# traning_shield_ver2.net
KiCad netlist of a schematic drawn in EAGLE
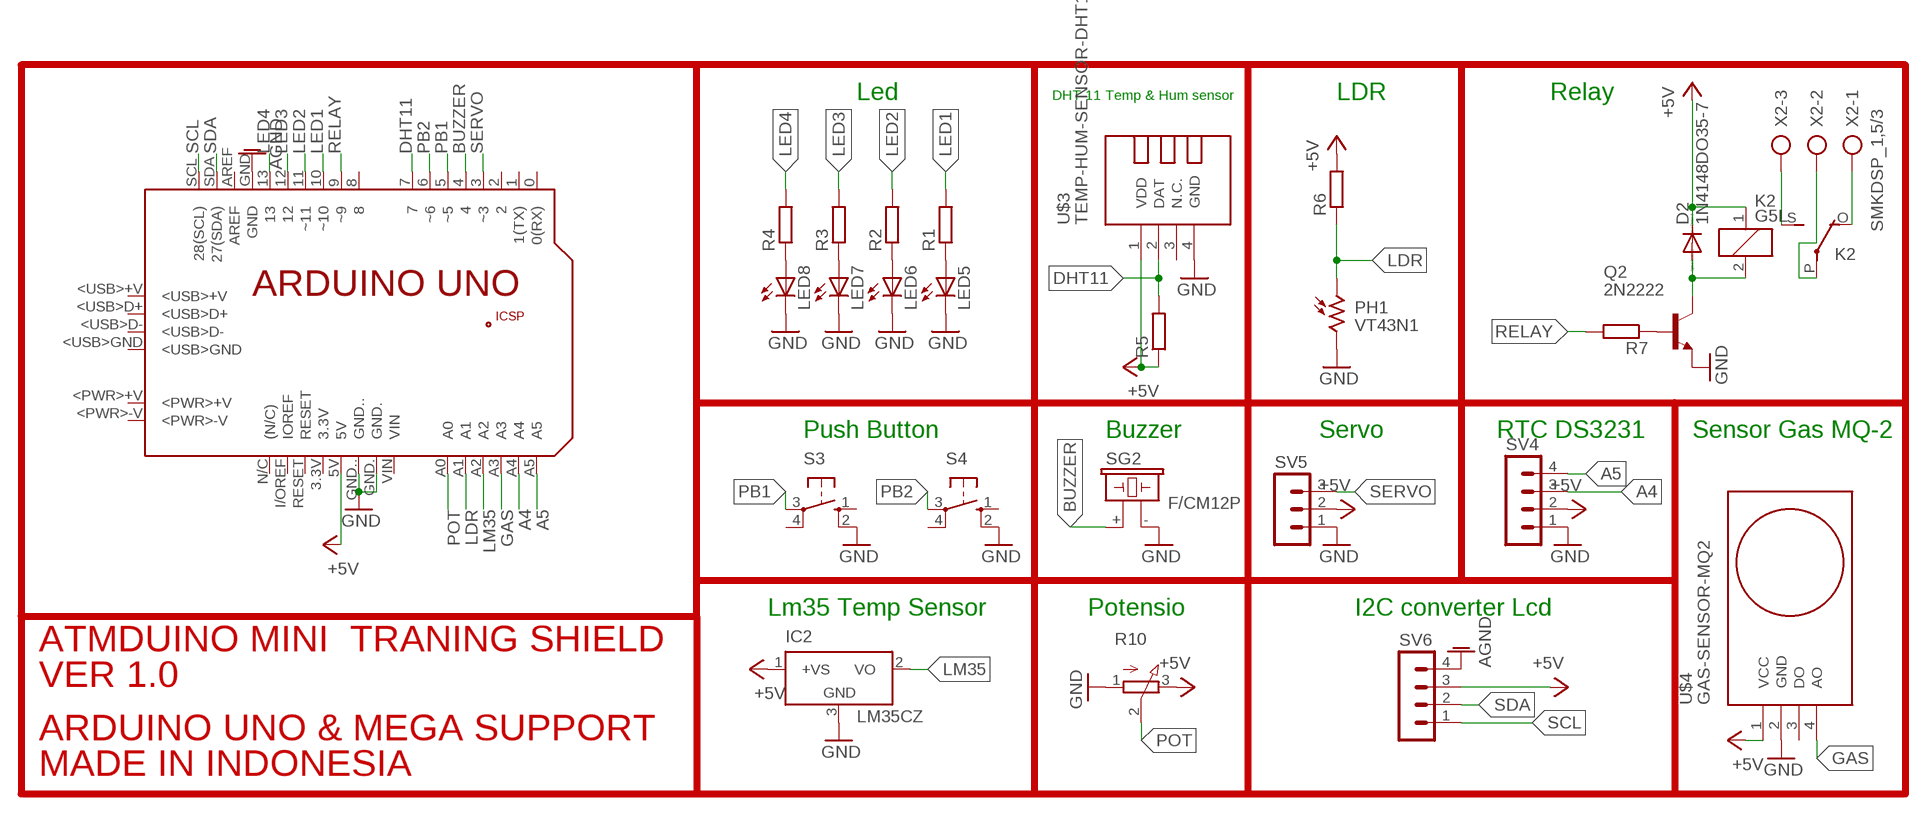
[diagram p0: schematic, sheet 1]

(export (version "E")
  (design (tool "Eeschema 10.0.6"))
  (components
    (comp (ref "D2")
      (value "1N4148DO35-7")
      (footprint "eagle-import:DO35-7")
      (libsource (lib "eagle-import") (part "1N4148DO35-7"))
    )
    (comp (ref "IC2")
      (value "LM35CZ")
      (footprint "eagle-import:TO92")
      (libsource (lib "eagle-import") (part "LM35CZ"))
    )
    (comp (ref "K2")
      (value "G5L")
      (footprint "eagle-import:G5LE")
      (libsource (lib "eagle-import") (part "G5L"))
    )
    (comp (ref "LED5")
      (value "LED5MM")
      (footprint "eagle-import:LED5MM")
      (libsource (lib "eagle-import") (part "LED5MM"))
    )
    (comp (ref "LED6")
      (value "LED5MM")
      (footprint "eagle-import:LED5MM")
      (libsource (lib "eagle-import") (part "LED5MM"))
    )
    (comp (ref "LED7")
      (value "LED5MM")
      (footprint "eagle-import:LED5MM")
      (libsource (lib "eagle-import") (part "LED5MM"))
    )
    (comp (ref "LED8")
      (value "LED5MM")
      (footprint "eagle-import:LED5MM")
      (libsource (lib "eagle-import") (part "LED5MM"))
    )
    (comp (ref "PCB2")
      (value "ARDUINO_UNO")
      (footprint "eagle-import:ARDUINO_UNO")
      (libsource (lib "eagle-import") (part "ARDUINO_UNO"))
    )
    (comp (ref "PH1")
      (value "VT43N1")
      (footprint "eagle-import:VT400")
      (libsource (lib "eagle-import") (part "VT43N1"))
    )
    (comp (ref "Q2")
      (value "2N2222")
      (footprint "eagle-import:TO18")
      (libsource (lib "eagle-import") (part "2N2222"))
    )
    (comp (ref "R1")
      (value "R-EU_0204/7")
      (footprint "eagle-import:0204_7")
      (libsource (lib "eagle-import") (part "R-EU_0204/7"))
    )
    (comp (ref "R2")
      (value "R-EU_0204/7")
      (footprint "eagle-import:0204_7")
      (libsource (lib "eagle-import") (part "R-EU_0204/7"))
    )
    (comp (ref "R3")
      (value "R-EU_0204/7")
      (footprint "eagle-import:0204_7")
      (libsource (lib "eagle-import") (part "R-EU_0204/7"))
    )
    (comp (ref "R4")
      (value "R-EU_0204/7")
      (footprint "eagle-import:0204_7")
      (libsource (lib "eagle-import") (part "R-EU_0204/7"))
    )
    (comp (ref "R5")
      (value "R-EU_0204/7")
      (footprint "eagle-import:0204_7")
      (libsource (lib "eagle-import") (part "R-EU_0204/7"))
    )
    (comp (ref "R6")
      (value "R-EU_0204/7")
      (footprint "eagle-import:0204_7")
      (libsource (lib "eagle-import") (part "R-EU_0204/7"))
    )
    (comp (ref "R7")
      (value "R-EU_0204/7")
      (footprint "eagle-import:0204_7")
      (libsource (lib "eagle-import") (part "R-EU_0204/7"))
    )
    (comp (ref "R10")
      (value "3RP/1610N")
      (footprint "eagle-import:3RP_1610N")
      (libsource (lib "eagle-import") (part "3RP/1610N"))
    )
    (comp (ref "S3")
      (value "10-XX")
      (footprint "eagle-import:B3F-10XX")
      (fields (field (name "MPN") "B3F-1000"))
      (libsource (lib "eagle-import") (part "10-XX"))
    )
    (comp (ref "S4")
      (value "10-XX")
      (footprint "eagle-import:B3F-10XX")
      (fields (field (name "MPN") "B3F-1000"))
      (libsource (lib "eagle-import") (part "10-XX"))
    )
    (comp (ref "SG2")
      (value "F/CM12P")
      (footprint "eagle-import:F_CM12P")
      (libsource (lib "eagle-import") (part "F/CM12P"))
    )
    (comp (ref "SV4")
      (value "MA04-1")
      (footprint "eagle-import:MA04-1")
      (libsource (lib "eagle-import") (part "MA04-1"))
    )
    (comp (ref "SV5")
      (value "MA03-1")
      (footprint "eagle-import:MA03-1")
      (libsource (lib "eagle-import") (part "MA03-1"))
    )
    (comp (ref "SV6")
      (value "MA04-1")
      (footprint "eagle-import:MA04-1")
      (libsource (lib "eagle-import") (part "MA04-1"))
    )
    (comp (ref "U$3")
      (value "TEMP-HUM-SENSOR-DHT11")
      (footprint "eagle-import:TEMP-HUM-SENSOR-DHT11")
      (libsource (lib "eagle-import") (part "TEMP-HUM-SENSOR-DHT11"))
    )
    (comp (ref "U$4")
      (value "GAS-SENSOR-MQ2")
      (footprint "eagle-import:GAS-SENSOR-MQ2")
      (libsource (lib "eagle-import") (part "GAS-SENSOR-MQ2"))
    )
    (comp (ref "X2")
      (value "SMKDSP_1,5/3")
      (footprint "eagle-import:SMKDSP_1,5_3")
      (fields (field (name "MF") "FARNELL") (field (name "MPN") "1733583"))
      (libsource (lib "eagle-import") (part "SMKDSP_1,5/3"))
    )
  )
  (nets
    (net (code "1") (name "+5V") (class "Default")
      (node (ref "D2") (pin "C") (pinfunction "C_C") (pintype "passive"))
      (node (ref "IC2") (pin "1") (pinfunction "+VS_1") (pintype "input"))
      (node (ref "K2") (pin "1") (pinfunction "1_1") (pintype "passive"))
      (node (ref "PCB2") (pin "5V") (pinfunction "5V_5V") (pintype "bidirectional"))
      (node (ref "R10") (pin "3") (pinfunction "E_3") (pintype "passive"))
      (node (ref "R5") (pin "1") (pinfunction "1_1") (pintype "passive"))
      (node (ref "R6") (pin "2") (pinfunction "2_2") (pintype "passive"))
      (node (ref "SV4") (pin "2") (pinfunction "2_2") (pintype "passive"))
      (node (ref "SV5") (pin "2") (pinfunction "2_2") (pintype "passive"))
      (node (ref "SV6") (pin "3") (pinfunction "3_3") (pintype "passive"))
      (node (ref "U$3") (pin "1") (pinfunction "VDD_1") (pintype "power_in"))
      (node (ref "U$4") (pin "1") (pinfunction "VCC_1") (pintype "power_in"))
    )
    (net (code "2") (name "A4") (class "Default")
      (node (ref "PCB2") (pin "A4") (pinfunction "A4_A4") (pintype "bidirectional"))
      (node (ref "SV4") (pin "3") (pinfunction "3_3") (pintype "passive"))
    )
    (net (code "3") (name "A5") (class "Default")
      (node (ref "PCB2") (pin "A5") (pinfunction "A5_A5") (pintype "bidirectional"))
      (node (ref "SV4") (pin "4") (pinfunction "4_4") (pintype "passive"))
    )
    (net (code "4") (name "AGND") (class "Default")
      (node (ref "PCB2") (pin "GND") (pinfunction "GND_GND") (pintype "bidirectional"))
      (node (ref "SV6") (pin "4") (pinfunction "4_4") (pintype "passive"))
    )
    (net (code "5") (name "BUZZER") (class "Default")
      (node (ref "PCB2") (pin "4") (pinfunction "4_4") (pintype "bidirectional"))
      (node (ref "SG2") (pin "+") (pinfunction "1_+") (pintype "passive"))
    )
    (net (code "6") (name "DHT11") (class "Default")
      (node (ref "PCB2") (pin "7") (pinfunction "7_7") (pintype "bidirectional"))
      (node (ref "R5") (pin "2") (pinfunction "2_2") (pintype "passive"))
      (node (ref "U$3") (pin "2") (pinfunction "DAT_2") (pintype "bidirectional"))
    )
    (net (code "7") (name "GAS") (class "Default")
      (node (ref "PCB2") (pin "A3") (pinfunction "A3_A3") (pintype "bidirectional"))
      (node (ref "U$4") (pin "4") (pinfunction "AO_4") (pintype "output"))
    )
    (net (code "8") (name "GND") (class "Default")
      (node (ref "IC2") (pin "3") (pinfunction "GND_3") (pintype "power_in"))
      (node (ref "LED5") (pin "K") (pinfunction "C_K") (pintype "passive"))
      (node (ref "LED6") (pin "K") (pinfunction "C_K") (pintype "passive"))
      (node (ref "LED7") (pin "K") (pinfunction "C_K") (pintype "passive"))
      (node (ref "LED8") (pin "K") (pinfunction "C_K") (pintype "passive"))
      (node (ref "PCB2") (pin "GND.") (pinfunction "GND._GND.") (pintype "bidirectional"))
      (node (ref "PCB2") (pin "GND..") (pinfunction "GND.._GND..") (pintype "bidirectional"))
      (node (ref "PH1") (pin "2") (pinfunction "2_2") (pintype "passive"))
      (node (ref "Q2") (pin "1") (pinfunction "E_1") (pintype "passive"))
      (node (ref "R10") (pin "1") (pinfunction "A_1") (pintype "passive"))
      (node (ref "S3") (pin "2") (pinfunction "S1_2") (pintype "passive"))
      (node (ref "S4") (pin "2") (pinfunction "S1_2") (pintype "passive"))
      (node (ref "SG2") (pin "-") (pinfunction "2_-") (pintype "passive"))
      (node (ref "SV4") (pin "1") (pinfunction "1_1") (pintype "passive"))
      (node (ref "SV5") (pin "1") (pinfunction "1_1") (pintype "passive"))
      (node (ref "U$3") (pin "4") (pinfunction "GND_4") (pintype "power_in"))
      (node (ref "U$4") (pin "2") (pinfunction "GND_2") (pintype "power_in"))
    )
    (net (code "9") (name "LDR") (class "Default")
      (node (ref "PCB2") (pin "A1") (pinfunction "A1_A1") (pintype "bidirectional"))
      (node (ref "PH1") (pin "1") (pinfunction "1_1") (pintype "passive"))
      (node (ref "R6") (pin "1") (pinfunction "1_1") (pintype "passive"))
    )
    (net (code "10") (name "LED1") (class "Default")
      (node (ref "PCB2") (pin "10") (pinfunction "~{10}_10") (pintype "bidirectional"))
      (node (ref "R1") (pin "2") (pinfunction "2_2") (pintype "passive"))
    )
    (net (code "11") (name "LED2") (class "Default")
      (node (ref "PCB2") (pin "11") (pinfunction "~{11}_11") (pintype "bidirectional"))
      (node (ref "R2") (pin "2") (pinfunction "2_2") (pintype "passive"))
    )
    (net (code "12") (name "LED3") (class "Default")
      (node (ref "PCB2") (pin "12") (pinfunction "12_12") (pintype "bidirectional"))
      (node (ref "R3") (pin "2") (pinfunction "2_2") (pintype "passive"))
    )
    (net (code "13") (name "LED4") (class "Default")
      (node (ref "PCB2") (pin "13") (pinfunction "13_13") (pintype "bidirectional"))
      (node (ref "R4") (pin "2") (pinfunction "2_2") (pintype "passive"))
    )
    (net (code "14") (name "LM35") (class "Default")
      (node (ref "IC2") (pin "2") (pinfunction "VO_2") (pintype "input"))
      (node (ref "PCB2") (pin "A2") (pinfunction "A2_A2") (pintype "bidirectional"))
    )
    (net (code "15") (name "Net-(LED5-PadA)") (class "Default")
      (node (ref "LED5") (pin "A") (pinfunction "A_A") (pintype "passive"))
      (node (ref "R1") (pin "1") (pinfunction "1_1") (pintype "passive"))
    )
    (net (code "16") (name "Net-(LED6-PadA)") (class "Default")
      (node (ref "LED6") (pin "A") (pinfunction "A_A") (pintype "passive"))
      (node (ref "R2") (pin "1") (pinfunction "1_1") (pintype "passive"))
    )
    (net (code "17") (name "Net-(LED7-PadA)") (class "Default")
      (node (ref "LED7") (pin "A") (pinfunction "A_A") (pintype "passive"))
      (node (ref "R3") (pin "1") (pinfunction "1_1") (pintype "passive"))
    )
    (net (code "18") (name "Net-(LED8-PadA)") (class "Default")
      (node (ref "LED8") (pin "A") (pinfunction "A_A") (pintype "passive"))
      (node (ref "R4") (pin "1") (pinfunction "1_1") (pintype "passive"))
    )
    (net (code "19") (name "Net-(Q2-B)") (class "Default")
      (node (ref "Q2") (pin "2") (pinfunction "B_2") (pintype "passive"))
      (node (ref "R7") (pin "1") (pinfunction "1_1") (pintype "passive"))
    )
    (net (code "20") (name "Net-(Q2-C)") (class "Default")
      (node (ref "D2") (pin "A") (pinfunction "A_A") (pintype "passive"))
      (node (ref "K2") (pin "2") (pinfunction "2_2") (pintype "passive"))
      (node (ref "Q2") (pin "3") (pinfunction "C_3") (pintype "passive"))
    )
    (net (code "21") (name "Net-(X2A-KL)") (class "Default")
      (node (ref "K2") (pin "O") (pinfunction "O_O") (pintype "passive"))
      (node (ref "X2") (pin "1") (pinfunction "KL_1") (pintype "passive"))
    )
    (net (code "22") (name "Net-(X2B-KL)") (class "Default")
      (node (ref "K2") (pin "P") (pinfunction "P_P") (pintype "passive"))
      (node (ref "X2") (pin "2") (pinfunction "KL_2") (pintype "passive"))
    )
    (net (code "23") (name "Net-(X2C-KL)") (class "Default")
      (node (ref "K2") (pin "S") (pinfunction "S_S") (pintype "passive"))
      (node (ref "X2") (pin "3") (pinfunction "KL_3") (pintype "passive"))
    )
    (net (code "24") (name "PB1") (class "Default")
      (node (ref "PCB2") (pin "5") (pinfunction "~{5}_5") (pintype "bidirectional"))
      (node (ref "S3") (pin "3") (pinfunction "P_3") (pintype "passive"))
    )
    (net (code "25") (name "PB2") (class "Default")
      (node (ref "PCB2") (pin "6") (pinfunction "~{6}_6") (pintype "bidirectional"))
      (node (ref "S4") (pin "3") (pinfunction "P_3") (pintype "passive"))
    )
    (net (code "26") (name "POT") (class "Default")
      (node (ref "PCB2") (pin "A0") (pinfunction "A0_A0") (pintype "bidirectional"))
      (node (ref "R10") (pin "2") (pinfunction "S_2") (pintype "passive"))
    )
    (net (code "27") (name "RELAY") (class "Default")
      (node (ref "PCB2") (pin "9") (pinfunction "~{9}_9") (pintype "bidirectional"))
      (node (ref "R7") (pin "2") (pinfunction "2_2") (pintype "passive"))
    )
    (net (code "28") (name "SCL") (class "Default")
      (node (ref "PCB2") (pin "SCL") (pinfunction "28(SCL)_SCL") (pintype "bidirectional"))
      (node (ref "SV6") (pin "1") (pinfunction "1_1") (pintype "passive"))
    )
    (net (code "29") (name "SDA") (class "Default")
      (node (ref "PCB2") (pin "SDA") (pinfunction "27(SDA)_SDA") (pintype "bidirectional"))
      (node (ref "SV6") (pin "2") (pinfunction "2_2") (pintype "passive"))
    )
    (net (code "30") (name "SERVO") (class "Default")
      (node (ref "PCB2") (pin "3") (pinfunction "~{3}_3") (pintype "bidirectional"))
      (node (ref "SV5") (pin "3") (pinfunction "3_3") (pintype "passive"))
    )
    (net (code "31") (name "unconnected-(PCB2-(N{slash}C)-PadN{slash}C)") (class "Default")
      (node (ref "PCB2") (pin "N/C") (pinfunction "(N/C)_N/C") (pintype "bidirectional"))
    )
    (net (code "32") (name "unconnected-(PCB2-0(RX)-Pad0)") (class "Default")
      (node (ref "PCB2") (pin "0") (pinfunction "0(RX)_0") (pintype "bidirectional"))
    )
    (net (code "33") (name "unconnected-(PCB2-1(TX)-Pad1)") (class "Default")
      (node (ref "PCB2") (pin "1") (pinfunction "1(TX)_1") (pintype "bidirectional"))
    )
    (net (code "34") (name "unconnected-(PCB2-IOREF-PadI{slash}OREF)") (class "Default")
      (node (ref "PCB2") (pin "I/OREF") (pinfunction "IOREF_I/OREF") (pintype "bidirectional"))
    )
    (net (code "35") (name "unconnected-(PCB2-Pad+5V)") (class "Default")
      (node (ref "PCB2") (pin "+5V") (pinfunction "+5V_+5V") (pintype "bidirectional"))
    )
    (net (code "36") (name "unconnected-(PCB2-Pad2)") (class "Default")
      (node (ref "PCB2") (pin "2") (pinfunction "2_2") (pintype "bidirectional"))
    )
    (net (code "37") (name "unconnected-(PCB2-Pad3.3V)") (class "Default")
      (node (ref "PCB2") (pin "3.3V") (pinfunction "3.3V_3.3V") (pintype "bidirectional"))
    )
    (net (code "38") (name "unconnected-(PCB2-Pad8)") (class "Default")
      (node (ref "PCB2") (pin "8") (pinfunction "8_8") (pintype "bidirectional"))
    )
    (net (code "39") (name "unconnected-(PCB2-Pad<PWR>+V)") (class "Default")
      (node (ref "PCB2") (pin "<PWR>+V") (pinfunction "<PWR>+V_<PWR>+V") (pintype "bidirectional"))
    )
    (net (code "40") (name "unconnected-(PCB2-Pad<PWR>-V)") (class "Default")
      (node (ref "PCB2") (pin "<PWR>-V") (pinfunction "<PWR>-V_<PWR>-V") (pintype "bidirectional"))
    )
    (net (code "41") (name "unconnected-(PCB2-Pad<USB>+V)") (class "Default")
      (node (ref "PCB2") (pin "<USB>+V") (pinfunction "<USB>+V_<USB>+V") (pintype "bidirectional"))
    )
    (net (code "42") (name "unconnected-(PCB2-Pad<USB>D+)") (class "Default")
      (node (ref "PCB2") (pin "<USB>D+") (pinfunction "<USB>D+_<USB>D+") (pintype "bidirectional"))
    )
    (net (code "43") (name "unconnected-(PCB2-Pad<USB>D-)") (class "Default")
      (node (ref "PCB2") (pin "<USB>D-") (pinfunction "<USB>D-_<USB>D-") (pintype "bidirectional"))
    )
    (net (code "44") (name "unconnected-(PCB2-Pad<USB>GND)") (class "Default")
      (node (ref "PCB2") (pin "<USB>GND") (pinfunction "<USB>GND_<USB>GND") (pintype "bidirectional"))
    )
    (net (code "45") (name "unconnected-(PCB2-PadAREF)") (class "Default")
      (node (ref "PCB2") (pin "AREF") (pinfunction "AREF_AREF") (pintype "bidirectional"))
    )
    (net (code "46") (name "unconnected-(PCB2-PadGND_)") (class "Default")
      (node (ref "PCB2") (pin "GND_") (pinfunction "GND__GND_") (pintype "bidirectional"))
    )
    (net (code "47") (name "unconnected-(PCB2-PadMISO)") (class "Default")
      (node (ref "PCB2") (pin "MISO") (pinfunction "MISO_MISO") (pintype "bidirectional"))
    )
    (net (code "48") (name "unconnected-(PCB2-PadMOSI)") (class "Default")
      (node (ref "PCB2") (pin "MOSI") (pinfunction "MOSI_MOSI") (pintype "bidirectional"))
    )
    (net (code "49") (name "unconnected-(PCB2-PadRESET)") (class "Default")
      (node (ref "PCB2") (pin "RESET") (pinfunction "RESET_RESET") (pintype "bidirectional"))
    )
    (net (code "50") (name "unconnected-(PCB2-PadRESET.)") (class "Default")
      (node (ref "PCB2") (pin "RESET.") (pinfunction "RESET._RESET.") (pintype "bidirectional"))
    )
    (net (code "51") (name "unconnected-(PCB2-PadSCK)") (class "Default")
      (node (ref "PCB2") (pin "SCK") (pinfunction "SCK_SCK") (pintype "bidirectional"))
    )
    (net (code "52") (name "unconnected-(PCB2-PadVIN)") (class "Default")
      (node (ref "PCB2") (pin "VIN") (pinfunction "VIN_VIN") (pintype "bidirectional"))
    )
    (net (code "53") (name "unconnected-(S3-P1-Pad4)") (class "Default")
      (node (ref "S3") (pin "4") (pinfunction "P1_4") (pintype "passive"))
    )
    (net (code "54") (name "unconnected-(S3-S-Pad1)") (class "Default")
      (node (ref "S3") (pin "1") (pinfunction "S_1") (pintype "passive"))
    )
    (net (code "55") (name "unconnected-(S4-P1-Pad4)") (class "Default")
      (node (ref "S4") (pin "4") (pinfunction "P1_4") (pintype "passive"))
    )
    (net (code "56") (name "unconnected-(S4-S-Pad1)") (class "Default")
      (node (ref "S4") (pin "1") (pinfunction "S_1") (pintype "passive"))
    )
    (net (code "57") (name "unconnected-(U$3-N.C.-Pad3)") (class "Default")
      (node (ref "U$3") (pin "3") (pinfunction "N.C._3") (pintype "passive"))
    )
    (net (code "58") (name "unconnected-(U$4-DO-Pad3)") (class "Default")
      (node (ref "U$4") (pin "3") (pinfunction "DO_3") (pintype "output"))
    )
  )
)
